# design.net
KiCad netlist of a schematic drawn in Altium Designer
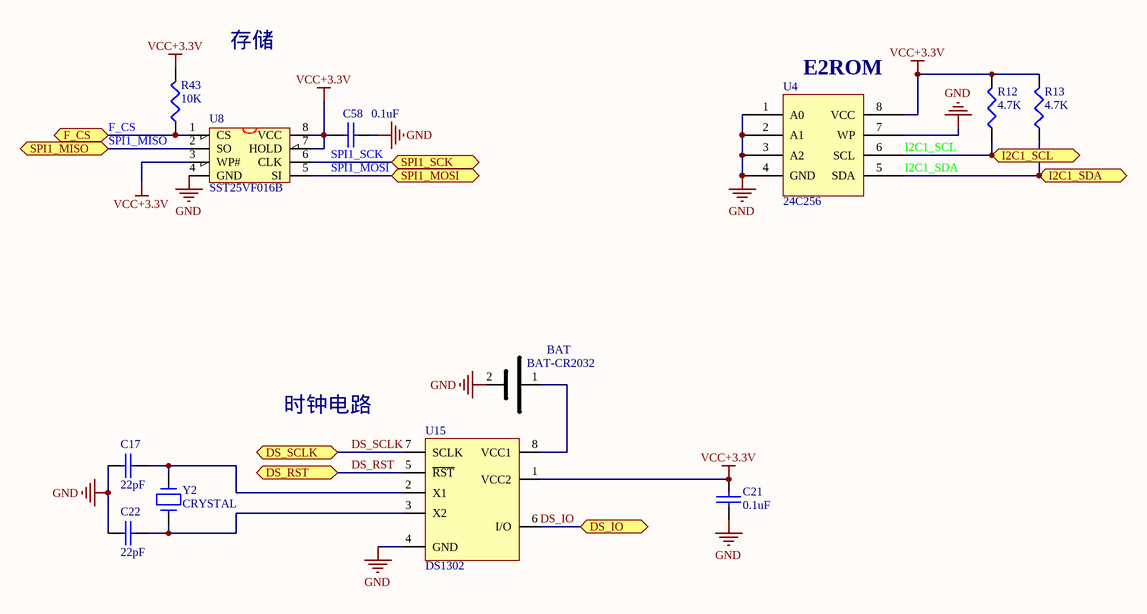
[diagram p0: 时钟、存储.SchDoc]

(export (version "E")
  (design (tool "Eeschema 10.0.6"))
  (components
    (comp (ref "BAT")
      (value "BAT-CR2032")
      (footprint "CR2032")
      (description "CR2032电池座")
      (libsource (lib "INSPUR_PCB") (part "BAT-CR2032"))
    )
    (comp (ref "C17")
      (value "22pF")
      (footprint "0603")
      (description "0603陶瓷贴片电容")
      (libsource (lib "INSPUR_PCB") (part "CAP-0603"))
    )
    (comp (ref "C21")
      (value "0.1uF")
      (footprint "0603")
      (description "0603陶瓷贴片电容")
      (libsource (lib "INSPUR_PCB") (part "CAP-0603"))
    )
    (comp (ref "C22")
      (value "22pF")
      (footprint "0603")
      (description "0603陶瓷贴片电容")
      (libsource (lib "INSPUR_PCB") (part "CAP-0603"))
    )
    (comp (ref "C58") (value "0.1uF") (footprint "0603") (libsource (lib "INSPUR_SCH") (part "CAP")))
    (comp (ref "R12")
      (value "4.7K")
      (footprint "0603")
      (description "陶瓷贴片电阻0603封装")
      (libsource (lib "INSPUR_PCB") (part "RES-0603"))
    )
    (comp (ref "R13")
      (value "4.7K")
      (footprint "0603")
      (description "陶瓷贴片电阻0603封装")
      (libsource (lib "INSPUR_PCB") (part "RES-0603"))
    )
    (comp (ref "R43")
      (value "10K")
      (footprint "0603")
      (description "陶瓷贴片电阻0603封装")
      (libsource (lib "INSPUR_PCB") (part "RES-0603"))
    )
    (comp (ref "U4")
      (value "24C256")
      (footprint "SO-8")
      (description "E2PROM")
      (libsource (lib "INSPUR_PCB") (part "24C256"))
    )
    (comp (ref "U8")
      (value "SST25VF016B")
      (footprint "SOIC-8")
      (description "SST25VF016  SPI FLASH")
      (libsource (lib "INSPUR_PCB") (part "SST25VF016B"))
    )
    (comp (ref "U15")
      (value "DS1302")
      (footprint "SO-8")
      (description "DS1302   时钟芯片")
      (libsource (lib "INSPUR_PCB") (part "DS1302"))
    )
    (comp (ref "Y2")
      (value "CRYSTAL")
      (footprint "CS206")
      (description "晶体振荡器2*6")
      (libsource (lib "INSPUR_PCB") (part "CRYSTAL"))
    )
  )
  (nets
    (net (code "1") (name "/DS_IO") (class "Default")
      (node (ref "U15") (pin "6") (pinfunction "I/O_6") (pintype "passive"))
    )
    (net (code "2") (name "/DS_RST") (class "Default")
      (node (ref "U15") (pin "5") (pinfunction "~{RST}_5") (pintype "passive"))
    )
    (net (code "3") (name "/DS_SCLK") (class "Default")
      (node (ref "U15") (pin "7") (pinfunction "SCLK_7") (pintype "passive"))
    )
    (net (code "4") (name "/F_CS") (class "Default")
      (node (ref "R43") (pin "1") (pinfunction "1_1") (pintype "passive"))
      (node (ref "U8") (pin "1") (pinfunction "CS_1") (pintype "passive"))
    )
    (net (code "5") (name "/I2C1_SCL") (class "Default")
      (node (ref "R12") (pin "1") (pinfunction "1_1") (pintype "passive"))
      (node (ref "U4") (pin "6") (pinfunction "SCL_6") (pintype "passive"))
    )
    (net (code "6") (name "/I2C1_SDA") (class "Default")
      (node (ref "R13") (pin "1") (pinfunction "1_1") (pintype "passive"))
      (node (ref "U4") (pin "5") (pinfunction "SDA_5") (pintype "passive"))
    )
    (net (code "7") (name "/SPI1_MISO") (class "Default")
      (node (ref "U8") (pin "2") (pinfunction "SO_2") (pintype "passive"))
    )
    (net (code "8") (name "/SPI1_MOSI") (class "Default")
      (node (ref "U8") (pin "5") (pinfunction "SI_5") (pintype "passive"))
    )
    (net (code "9") (name "/SPI1_SCK") (class "Default")
      (node (ref "U8") (pin "6") (pinfunction "CLK_6") (pintype "passive"))
    )
    (net (code "10") (name "GND") (class "Default")
      (node (ref "BAT") (pin "2") (pintype "passive"))
      (node (ref "C17") (pin "1") (pinfunction "1_1") (pintype "passive"))
      (node (ref "C21") (pin "1") (pinfunction "1_1") (pintype "passive"))
      (node (ref "C22") (pin "1") (pinfunction "1_1") (pintype "passive"))
      (node (ref "C58") (pin "1") (pinfunction "1_1") (pintype "passive"))
      (node (ref "U15") (pin "4") (pinfunction "GND_4") (pintype "passive"))
      (node (ref "U4") (pin "1") (pinfunction "A0_1") (pintype "passive"))
      (node (ref "U4") (pin "2") (pinfunction "A1_2") (pintype "passive"))
      (node (ref "U4") (pin "3") (pinfunction "A2_3") (pintype "passive"))
      (node (ref "U4") (pin "4") (pinfunction "GND_4") (pintype "passive"))
      (node (ref "U4") (pin "7") (pinfunction "WP_7") (pintype "passive"))
      (node (ref "U8") (pin "4") (pinfunction "GND_4") (pintype "passive"))
    )
    (net (code "11") (name "Net-(U15-VCC1)") (class "Default")
      (node (ref "BAT") (pin "1") (pintype "passive"))
      (node (ref "U15") (pin "8") (pinfunction "VCC1_8") (pintype "passive"))
    )
    (net (code "12") (name "Net-(U15-X1)") (class "Default")
      (node (ref "C17") (pin "2") (pinfunction "2_2") (pintype "passive"))
      (node (ref "U15") (pin "2") (pinfunction "X1_2") (pintype "passive"))
      (node (ref "Y2") (pin "2") (pinfunction "2_2") (pintype "passive"))
    )
    (net (code "13") (name "Net-(U15-X2)") (class "Default")
      (node (ref "C22") (pin "2") (pinfunction "2_2") (pintype "passive"))
      (node (ref "U15") (pin "3") (pinfunction "X2_3") (pintype "passive"))
      (node (ref "Y2") (pin "1") (pinfunction "1_1") (pintype "passive"))
    )
    (net (code "14") (name "VCC+3.3V") (class "Default")
      (node (ref "C21") (pin "2") (pinfunction "2_2") (pintype "passive"))
      (node (ref "C58") (pin "2") (pinfunction "2_2") (pintype "passive"))
      (node (ref "R12") (pin "2") (pinfunction "2_2") (pintype "passive"))
      (node (ref "R13") (pin "2") (pinfunction "2_2") (pintype "passive"))
      (node (ref "R43") (pin "2") (pinfunction "2_2") (pintype "passive"))
      (node (ref "U15") (pin "1") (pinfunction "VCC2_1") (pintype "passive"))
      (node (ref "U4") (pin "8") (pinfunction "VCC_8") (pintype "passive"))
      (node (ref "U8") (pin "3") (pinfunction "WP#_3") (pintype "passive"))
      (node (ref "U8") (pin "7") (pinfunction "HOLD_7") (pintype "passive"))
      (node (ref "U8") (pin "8") (pinfunction "VCC_8") (pintype "passive"))
    )
  )
)
